# with_usb_small.net
KiCad netlist of a schematic drawn in EAGLE
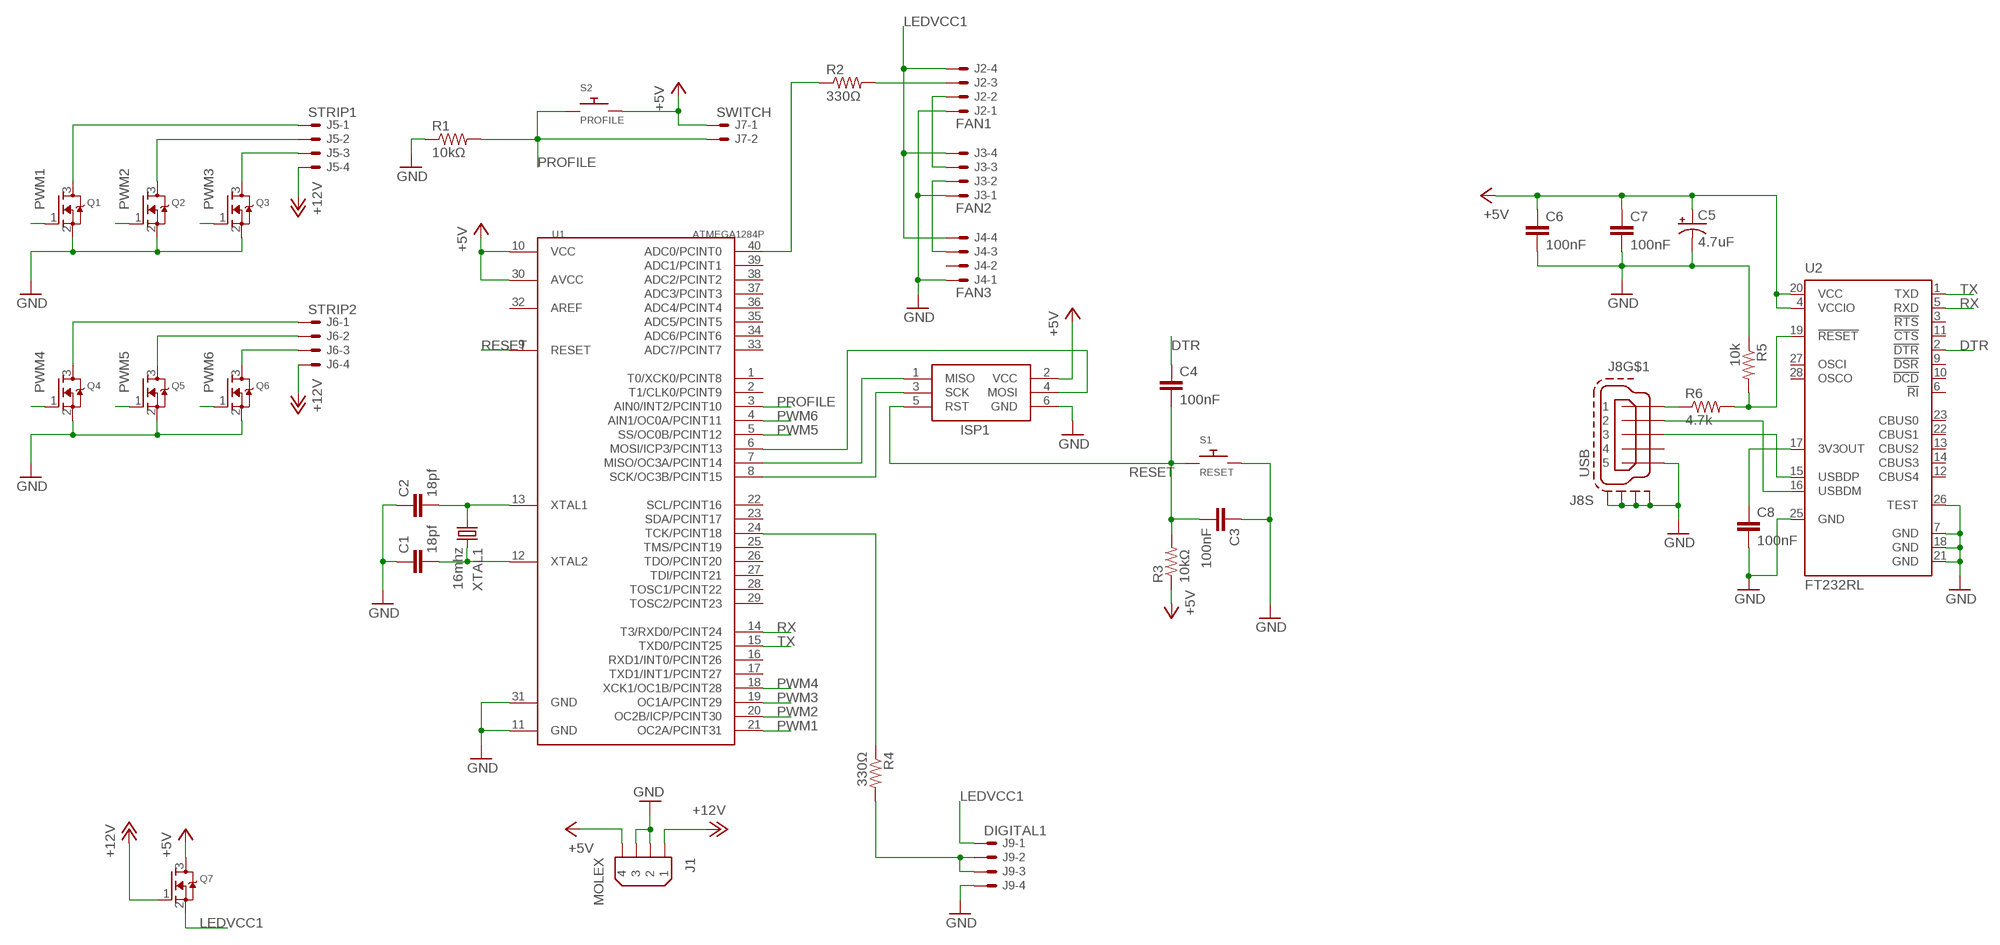
[diagram p0: schematic, sheet 1]

(export (version "E")
  (design (tool "Eeschema 10.0.6"))
  (components
    (comp (ref "C1")
      (value "18pf")
      (footprint "eagle-import:C0805")
      (libsource (lib "eagle-import") (part "C-EUC0805"))
    )
    (comp (ref "C2")
      (value "18pf")
      (footprint "eagle-import:C0805")
      (libsource (lib "eagle-import") (part "C"))
    )
    (comp (ref "C3")
      (value "100nF")
      (footprint "eagle-import:C0805")
      (libsource (lib "eagle-import") (part "C-EUC0805"))
    )
    (comp (ref "C4")
      (value "100nF")
      (footprint "eagle-import:C0805")
      (libsource (lib "eagle-import") (part "C-EUC0805"))
    )
    (comp (ref "C5")
      (value "4.7uF")
      (footprint "eagle-import:153CLV-0505")
      (libsource (lib "eagle-import") (part "CPOL-US153CLV-0505"))
    )
    (comp (ref "C6")
      (value "100nF")
      (footprint "eagle-import:C0805")
      (libsource (lib "eagle-import") (part "resistor_348_C-EUC0805"))
    )
    (comp (ref "C7")
      (value "100nF")
      (footprint "eagle-import:C0805")
      (libsource (lib "eagle-import") (part "resistor_348_C-EUC0805"))
    )
    (comp (ref "C8")
      (value "100nF")
      (footprint "eagle-import:C0805")
      (libsource (lib "eagle-import") (part "resistor_348_C-EUC0805"))
    )
    (comp (ref "ISP1")
      (value "AVRISP-6")
      (footprint "eagle-import:AVRISP")
      (libsource (lib "eagle-import") (part "AVRISP-6"))
    )
    (comp (ref "J1")
      (value "MOLEX")
      (footprint "eagle-import:9090-4R")
      (libsource (lib "eagle-import") (part "9090-4R"))
    )
    (comp (ref "J2")
      (value "FAN1")
      (footprint "eagle-import:22-23-2041")
      (fields (field (name "MF") "MOLEX") (field (name "MPN") "22-23-2041"))
      (libsource (lib "eagle-import") (part "22-23-2041"))
    )
    (comp (ref "J3")
      (value "FAN2")
      (footprint "eagle-import:22-23-2041")
      (fields (field (name "MF") "MOLEX") (field (name "MPN") "22-23-2041"))
      (libsource (lib "eagle-import") (part "22-23-2041"))
    )
    (comp (ref "J4")
      (value "FAN3")
      (footprint "eagle-import:22-23-2041")
      (fields (field (name "MF") "MOLEX") (field (name "MPN") "22-23-2041"))
      (libsource (lib "eagle-import") (part "22-23-2041"))
    )
    (comp (ref "J5")
      (value "STRIP1")
      (footprint "eagle-import:22-23-2041")
      (fields (field (name "MF") "MOLEX") (field (name "MPN") "22-23-2041"))
      (libsource (lib "eagle-import") (part "22-23-2041"))
    )
    (comp (ref "J6")
      (value "STRIP2")
      (footprint "eagle-import:22-23-2041")
      (fields (field (name "MF") "MOLEX") (field (name "MPN") "22-23-2041"))
      (libsource (lib "eagle-import") (part "22-23-2041"))
    )
    (comp (ref "J7")
      (value "SWITCH")
      (footprint "eagle-import:22-23-2021")
      (fields (field (name "MF") "MOLEX") (field (name "MPN") "22-23-2021"))
      (libsource (lib "eagle-import") (part "22-23-2021"))
    )
    (comp (ref "J8")
      (value "USB")
      (footprint "eagle-import:32005-201")
      (libsource (lib "eagle-import") (part "MINI-USB-SCHIELD-32005-201"))
    )
    (comp (ref "J9")
      (value "DIGITAL1")
      (footprint "eagle-import:22-23-2041")
      (fields (field (name "MF") "MOLEX") (field (name "MPN") "22-23-2041"))
      (libsource (lib "eagle-import") (part "22-23-2041"))
    )
    (comp (ref "Q1")
      (value "MOSFET-NREFLOW")
      (footprint "eagle-import:SOT23")
      (libsource (lib "eagle-import") (part "MOSFET-NREFLOW"))
    )
    (comp (ref "Q2")
      (value "MOSFET-NREFLOW")
      (footprint "eagle-import:SOT23")
      (libsource (lib "eagle-import") (part "MOSFET-NREFLOW"))
    )
    (comp (ref "Q3")
      (value "MOSFET-NREFLOW")
      (footprint "eagle-import:SOT23")
      (libsource (lib "eagle-import") (part "MOSFET-NREFLOW"))
    )
    (comp (ref "Q4")
      (value "MOSFET-NREFLOW")
      (footprint "eagle-import:SOT23")
      (libsource (lib "eagle-import") (part "MOSFET-NREFLOW"))
    )
    (comp (ref "Q5")
      (value "MOSFET-NREFLOW")
      (footprint "eagle-import:SOT23")
      (libsource (lib "eagle-import") (part "MOSFET-NREFLOW"))
    )
    (comp (ref "Q6")
      (value "MOSFET-NREFLOW")
      (footprint "eagle-import:SOT23")
      (libsource (lib "eagle-import") (part "MOSFET-NREFLOW"))
    )
    (comp (ref "Q7")
      (value "MOSFET-NREFLOW")
      (footprint "eagle-import:SOT23")
      (libsource (lib "eagle-import") (part "MOSFET-NREFLOW"))
    )
    (comp (ref "R1")
      (value "10kΩ")
      (footprint "eagle-import:M0805")
      (libsource (lib "eagle-import") (part "R-US_M0805"))
    )
    (comp (ref "R2")
      (value "330Ω")
      (footprint "eagle-import:M0805")
      (libsource (lib "eagle-import") (part "R-US_M0805"))
    )
    (comp (ref "R3")
      (value "10kΩ")
      (footprint "eagle-import:M0805")
      (libsource (lib "eagle-import") (part "R-US_M0805"))
    )
    (comp (ref "R4")
      (value "330Ω")
      (footprint "eagle-import:M0805")
      (libsource (lib "eagle-import") (part "R-US_M0805"))
    )
    (comp (ref "R5")
      (value "10k")
      (footprint "eagle-import:R0805")
      (libsource (lib "eagle-import") (part "resistor_348_R-US_R0805"))
    )
    (comp (ref "R6")
      (value "4.7k")
      (footprint "eagle-import:R0805")
      (libsource (lib "eagle-import") (part "resistor_348_R-US_R0805"))
    )
    (comp (ref "S1")
      (value "RESET")
      (footprint "eagle-import:B3F-1000")
      (libsource (lib "eagle-import") (part "BUTTON"))
    )
    (comp (ref "S2")
      (value "PROFILE")
      (footprint "eagle-import:B3F-1000")
      (libsource (lib "eagle-import") (part "BUTTON"))
    )
    (comp (ref "U1")
      (value "ATMEGA1284P")
      (footprint "eagle-import:DIL40")
      (libsource (lib "eagle-import") (part "MEGA1284P"))
    )
    (comp (ref "U2")
      (value "FT232RL")
      (footprint "eagle-import:SSOP28")
      (libsource (lib "eagle-import") (part "FT232RL"))
    )
    (comp (ref "XTAL1")
      (value "16mhz")
      (footprint "eagle-import:HC49U-V")
      (libsource (lib "eagle-import") (part "CRYSTALHC49U-V"))
    )
  )
  (nets
    (net (code "1") (name "+5V") (class "Default")
      (node (ref "C5") (pin "+") (pinfunction "+_+") (pintype "passive"))
      (node (ref "C6") (pin "1") (pinfunction "1_1") (pintype "passive"))
      (node (ref "C7") (pin "1") (pinfunction "1_1") (pintype "passive"))
      (node (ref "ISP1") (pin "2") (pinfunction "VCC_2") (pintype "power_in"))
      (node (ref "J1") (pin "4") (pinfunction "4_4") (pintype "passive"))
      (node (ref "J7") (pin "1") (pinfunction "S_1") (pintype "passive"))
      (node (ref "Q7") (pin "3") (pinfunction "D_3") (pintype "bidirectional"))
      (node (ref "R3") (pin "1") (pinfunction "1_1") (pintype "passive"))
      (node (ref "S2") (pin "3") (pinfunction "P$2_3") (pintype "passive"))
      (node (ref "S2") (pin "4") (pinfunction "P$2_4") (pintype "passive"))
      (node (ref "U1") (pin "10") (pinfunction "VCC_10") (pintype "bidirectional"))
      (node (ref "U1") (pin "30") (pinfunction "AVCC_30") (pintype "bidirectional"))
      (node (ref "U2") (pin "20") (pinfunction "VCC_20") (pintype "power_in"))
      (node (ref "U2") (pin "4") (pinfunction "VCCIO_4") (pintype "power_in"))
    )
    (net (code "2") (name "+12V") (class "Default")
      (node (ref "J1") (pin "1") (pinfunction "1_1") (pintype "passive"))
      (node (ref "J5") (pin "4") (pinfunction "S_4") (pintype "passive"))
      (node (ref "J6") (pin "4") (pinfunction "S_4") (pintype "passive"))
      (node (ref "Q7") (pin "1") (pinfunction "G_1") (pintype "bidirectional"))
    )
    (net (code "3") (name "/DTR") (class "Default")
      (node (ref "C4") (pin "1") (pinfunction "1_1") (pintype "passive"))
      (node (ref "U2") (pin "2") (pinfunction "~{DTR}_2") (pintype "output"))
    )
    (net (code "4") (name "/LEDVCC1") (class "Default")
      (node (ref "J2") (pin "4") (pinfunction "S_4") (pintype "passive"))
      (node (ref "J3") (pin "4") (pinfunction "S_4") (pintype "passive"))
      (node (ref "J4") (pin "4") (pinfunction "S_4") (pintype "passive"))
      (node (ref "J9") (pin "1") (pinfunction "S_1") (pintype "passive"))
      (node (ref "Q7") (pin "2") (pinfunction "S_2") (pintype "bidirectional"))
    )
    (net (code "5") (name "/PROFILE") (class "Default")
      (node (ref "J7") (pin "2") (pinfunction "S_2") (pintype "passive"))
      (node (ref "R1") (pin "2") (pinfunction "2_2") (pintype "passive"))
      (node (ref "S2") (pin "1") (pinfunction "P$1_1") (pintype "passive"))
      (node (ref "S2") (pin "2") (pinfunction "P$1_2") (pintype "passive"))
      (node (ref "U1") (pin "3") (pinfunction "AIN0/INT2/PCINT10_3") (pintype "bidirectional"))
    )
    (net (code "6") (name "/PWM1") (class "Default")
      (node (ref "Q1") (pin "1") (pinfunction "G_1") (pintype "bidirectional"))
      (node (ref "U1") (pin "21") (pinfunction "OC2A/PCINT31_21") (pintype "bidirectional"))
    )
    (net (code "7") (name "/PWM2") (class "Default")
      (node (ref "Q2") (pin "1") (pinfunction "G_1") (pintype "bidirectional"))
      (node (ref "U1") (pin "20") (pinfunction "OC2B/ICP/PCINT30_20") (pintype "bidirectional"))
    )
    (net (code "8") (name "/PWM3") (class "Default")
      (node (ref "Q3") (pin "1") (pinfunction "G_1") (pintype "bidirectional"))
      (node (ref "U1") (pin "19") (pinfunction "OC1A/PCINT29_19") (pintype "bidirectional"))
    )
    (net (code "9") (name "/PWM4") (class "Default")
      (node (ref "Q4") (pin "1") (pinfunction "G_1") (pintype "bidirectional"))
      (node (ref "U1") (pin "18") (pinfunction "XCK1/OC1B/PCINT28_18") (pintype "bidirectional"))
    )
    (net (code "10") (name "/PWM5") (class "Default")
      (node (ref "Q5") (pin "1") (pinfunction "G_1") (pintype "bidirectional"))
      (node (ref "U1") (pin "5") (pinfunction "SS/OC0B/PCINT12_5") (pintype "bidirectional"))
    )
    (net (code "11") (name "/PWM6") (class "Default")
      (node (ref "Q6") (pin "1") (pinfunction "G_1") (pintype "bidirectional"))
      (node (ref "U1") (pin "4") (pinfunction "AIN1/OC0A/PCINT11_4") (pintype "bidirectional"))
    )
    (net (code "12") (name "/RESET") (class "Default")
      (node (ref "C3") (pin "2") (pinfunction "2_2") (pintype "passive"))
      (node (ref "C4") (pin "2") (pinfunction "2_2") (pintype "passive"))
      (node (ref "ISP1") (pin "5") (pinfunction "RST_5") (pintype "output"))
      (node (ref "R3") (pin "2") (pinfunction "2_2") (pintype "passive"))
      (node (ref "S1") (pin "1") (pinfunction "P$1_1") (pintype "passive"))
      (node (ref "S1") (pin "2") (pinfunction "P$1_2") (pintype "passive"))
      (node (ref "U1") (pin "9") (pinfunction "RESET_9") (pintype "bidirectional"))
    )
    (net (code "13") (name "/RX") (class "Default")
      (node (ref "U1") (pin "14") (pinfunction "T3/RXD0/PCINT24_14") (pintype "bidirectional"))
      (node (ref "U2") (pin "5") (pinfunction "RXD_5") (pintype "input"))
    )
    (net (code "14") (name "/TX") (class "Default")
      (node (ref "U1") (pin "15") (pinfunction "TXD0/PCINT25_15") (pintype "bidirectional"))
      (node (ref "U2") (pin "1") (pinfunction "TXD_1") (pintype "output"))
    )
    (net (code "15") (name "GND") (class "Default")
      (node (ref "C1") (pin "1") (pinfunction "1_1") (pintype "passive"))
      (node (ref "C2") (pin "1") (pinfunction "1_1") (pintype "passive"))
      (node (ref "C3") (pin "1") (pinfunction "1_1") (pintype "passive"))
      (node (ref "C5") (pin "-") (pinfunction "-_-") (pintype "passive"))
      (node (ref "C6") (pin "2") (pinfunction "2_2") (pintype "passive"))
      (node (ref "C7") (pin "2") (pinfunction "2_2") (pintype "passive"))
      (node (ref "C8") (pin "2") (pinfunction "2_2") (pintype "passive"))
      (node (ref "ISP1") (pin "6") (pinfunction "GND_6") (pintype "power_in"))
      (node (ref "J1") (pin "2") (pinfunction "2_2") (pintype "passive"))
      (node (ref "J1") (pin "3") (pinfunction "3_3") (pintype "passive"))
      (node (ref "J2") (pin "1") (pinfunction "S_1") (pintype "passive"))
      (node (ref "J3") (pin "1") (pinfunction "S_1") (pintype "passive"))
      (node (ref "J4") (pin "1") (pinfunction "S_1") (pintype "passive"))
      (node (ref "J8") (pin "5") (pinfunction "5_5") (pintype "passive"))
      (node (ref "J8") (pin "M1") (pinfunction "S1_M1") (pintype "passive"))
      (node (ref "J8") (pin "M2") (pinfunction "S2_M2") (pintype "passive"))
      (node (ref "J8") (pin "M3") (pinfunction "S3_M3") (pintype "passive"))
      (node (ref "J8") (pin "M4") (pinfunction "S4_M4") (pintype "passive"))
      (node (ref "J9") (pin "4") (pinfunction "S_4") (pintype "passive"))
      (node (ref "Q1") (pin "2") (pinfunction "S_2") (pintype "bidirectional"))
      (node (ref "Q2") (pin "2") (pinfunction "S_2") (pintype "bidirectional"))
      (node (ref "Q3") (pin "2") (pinfunction "S_2") (pintype "bidirectional"))
      (node (ref "Q4") (pin "2") (pinfunction "S_2") (pintype "bidirectional"))
      (node (ref "Q5") (pin "2") (pinfunction "S_2") (pintype "bidirectional"))
      (node (ref "Q6") (pin "2") (pinfunction "S_2") (pintype "bidirectional"))
      (node (ref "R1") (pin "1") (pinfunction "1_1") (pintype "passive"))
      (node (ref "R5") (pin "1") (pinfunction "1_1") (pintype "passive"))
      (node (ref "S1") (pin "3") (pinfunction "P$2_3") (pintype "passive"))
      (node (ref "S1") (pin "4") (pinfunction "P$2_4") (pintype "passive"))
      (node (ref "U1") (pin "11") (pinfunction "GND_11") (pintype "bidirectional"))
      (node (ref "U1") (pin "31") (pinfunction "GND_31") (pintype "bidirectional"))
      (node (ref "U2") (pin "18") (pinfunction "GND_18") (pintype "power_in"))
      (node (ref "U2") (pin "21") (pinfunction "GND_21") (pintype "power_in"))
      (node (ref "U2") (pin "25") (pinfunction "GND_25") (pintype "power_in"))
      (node (ref "U2") (pin "26") (pinfunction "TEST_26") (pintype "input"))
      (node (ref "U2") (pin "7") (pinfunction "GND_7") (pintype "power_in"))
    )
    (net (code "16") (name "Net-(ISP1-MISO)") (class "Default")
      (node (ref "ISP1") (pin "1") (pinfunction "MISO_1") (pintype "input"))
      (node (ref "U1") (pin "7") (pinfunction "MISO/OC3A/PCINT14_7") (pintype "bidirectional"))
    )
    (net (code "17") (name "Net-(ISP1-MOSI)") (class "Default")
      (node (ref "ISP1") (pin "4") (pinfunction "MOSI_4") (pintype "output"))
      (node (ref "U1") (pin "6") (pinfunction "MOSI/ICP3/PCINT13_6") (pintype "bidirectional"))
    )
    (net (code "18") (name "Net-(ISP1-SCK)") (class "Default")
      (node (ref "ISP1") (pin "3") (pinfunction "SCK_3") (pintype "output"))
      (node (ref "U1") (pin "8") (pinfunction "SCK/OC3B/PCINT15_8") (pintype "bidirectional"))
    )
    (net (code "19") (name "Net-(J2B-S)") (class "Default")
      (node (ref "J2") (pin "2") (pinfunction "S_2") (pintype "passive"))
      (node (ref "J3") (pin "3") (pinfunction "S_3") (pintype "passive"))
    )
    (net (code "20") (name "Net-(J2C-S)") (class "Default")
      (node (ref "J2") (pin "3") (pinfunction "S_3") (pintype "passive"))
      (node (ref "R2") (pin "2") (pinfunction "2_2") (pintype "passive"))
    )
    (net (code "21") (name "Net-(J3B-S)") (class "Default")
      (node (ref "J3") (pin "2") (pinfunction "S_2") (pintype "passive"))
      (node (ref "J4") (pin "3") (pinfunction "S_3") (pintype "passive"))
    )
    (net (code "22") (name "Net-(J5A-S)") (class "Default")
      (node (ref "J5") (pin "1") (pinfunction "S_1") (pintype "passive"))
      (node (ref "Q1") (pin "3") (pinfunction "D_3") (pintype "bidirectional"))
    )
    (net (code "23") (name "Net-(J5B-S)") (class "Default")
      (node (ref "J5") (pin "2") (pinfunction "S_2") (pintype "passive"))
      (node (ref "Q2") (pin "3") (pinfunction "D_3") (pintype "bidirectional"))
    )
    (net (code "24") (name "Net-(J5C-S)") (class "Default")
      (node (ref "J5") (pin "3") (pinfunction "S_3") (pintype "passive"))
      (node (ref "Q3") (pin "3") (pinfunction "D_3") (pintype "bidirectional"))
    )
    (net (code "25") (name "Net-(J6A-S)") (class "Default")
      (node (ref "J6") (pin "1") (pinfunction "S_1") (pintype "passive"))
      (node (ref "Q4") (pin "3") (pinfunction "D_3") (pintype "bidirectional"))
    )
    (net (code "26") (name "Net-(J6B-S)") (class "Default")
      (node (ref "J6") (pin "2") (pinfunction "S_2") (pintype "passive"))
      (node (ref "Q5") (pin "3") (pinfunction "D_3") (pintype "bidirectional"))
    )
    (net (code "27") (name "Net-(J6C-S)") (class "Default")
      (node (ref "J6") (pin "3") (pinfunction "S_3") (pintype "passive"))
      (node (ref "Q6") (pin "3") (pinfunction "D_3") (pintype "bidirectional"))
    )
    (net (code "28") (name "Net-(J8-Pad1)") (class "Default")
      (node (ref "J8") (pin "1") (pinfunction "1_1") (pintype "passive"))
      (node (ref "R6") (pin "1") (pinfunction "1_1") (pintype "passive"))
    )
    (net (code "29") (name "Net-(J9B-S)") (class "Default")
      (node (ref "J9") (pin "2") (pinfunction "S_2") (pintype "passive"))
      (node (ref "J9") (pin "3") (pinfunction "S_3") (pintype "passive"))
      (node (ref "R4") (pin "2") (pinfunction "2_2") (pintype "passive"))
    )
    (net (code "30") (name "Net-(U1-ADC0{slash}PCINT0)") (class "Default")
      (node (ref "R2") (pin "1") (pinfunction "1_1") (pintype "passive"))
      (node (ref "U1") (pin "40") (pinfunction "ADC0/PCINT0_40") (pintype "bidirectional"))
    )
    (net (code "31") (name "Net-(U1-TCK{slash}PCINT18)") (class "Default")
      (node (ref "R4") (pin "1") (pinfunction "1_1") (pintype "passive"))
      (node (ref "U1") (pin "24") (pinfunction "TCK/PCINT18_24") (pintype "bidirectional"))
    )
    (net (code "32") (name "Net-(U1-XTAL1)") (class "Default")
      (node (ref "C2") (pin "2") (pinfunction "2_2") (pintype "passive"))
      (node (ref "U1") (pin "13") (pinfunction "XTAL1_13") (pintype "bidirectional"))
      (node (ref "XTAL1") (pin "1") (pinfunction "1_1") (pintype "passive"))
    )
    (net (code "33") (name "Net-(U1-XTAL2)") (class "Default")
      (node (ref "C1") (pin "2") (pinfunction "2_2") (pintype "passive"))
      (node (ref "U1") (pin "12") (pinfunction "XTAL2_12") (pintype "bidirectional"))
      (node (ref "XTAL1") (pin "2") (pinfunction "2_2") (pintype "passive"))
    )
    (net (code "34") (name "Net-(U2-3V3OUT)") (class "Default")
      (node (ref "C8") (pin "1") (pinfunction "1_1") (pintype "passive"))
      (node (ref "U2") (pin "17") (pinfunction "3V3OUT_17") (pintype "output"))
    )
    (net (code "35") (name "Net-(U2-USBDM)") (class "Default")
      (node (ref "J8") (pin "2") (pinfunction "2_2") (pintype "passive"))
      (node (ref "U2") (pin "16") (pinfunction "USBDM_16") (pintype "bidirectional"))
    )
    (net (code "36") (name "Net-(U2-USBDP)") (class "Default")
      (node (ref "J8") (pin "3") (pinfunction "3_3") (pintype "passive"))
      (node (ref "U2") (pin "15") (pinfunction "USBDP_15") (pintype "bidirectional"))
    )
    (net (code "37") (name "Net-(U2-~{RESET})") (class "Default")
      (node (ref "R5") (pin "2") (pinfunction "2_2") (pintype "passive"))
      (node (ref "R6") (pin "2") (pinfunction "2_2") (pintype "passive"))
      (node (ref "U2") (pin "19") (pinfunction "~{RESET}_19") (pintype "input"))
    )
    (net (code "38") (name "unconnected-(J4B-S-Pad2)") (class "Default")
      (node (ref "J4") (pin "2") (pinfunction "S_2") (pintype "passive"))
    )
    (net (code "39") (name "unconnected-(J8-Pad4)") (class "Default")
      (node (ref "J8") (pin "4") (pinfunction "4_4") (pintype "passive"))
    )
    (net (code "40") (name "unconnected-(U1-ADC1{slash}PCINT1-Pad39)") (class "Default")
      (node (ref "U1") (pin "39") (pinfunction "ADC1/PCINT1_39") (pintype "bidirectional"))
    )
    (net (code "41") (name "unconnected-(U1-ADC2{slash}PCINT2-Pad38)") (class "Default")
      (node (ref "U1") (pin "38") (pinfunction "ADC2/PCINT2_38") (pintype "bidirectional"))
    )
    (net (code "42") (name "unconnected-(U1-ADC3{slash}PCINT3-Pad37)") (class "Default")
      (node (ref "U1") (pin "37") (pinfunction "ADC3/PCINT3_37") (pintype "bidirectional"))
    )
    (net (code "43") (name "unconnected-(U1-ADC4{slash}PCINT4-Pad36)") (class "Default")
      (node (ref "U1") (pin "36") (pinfunction "ADC4/PCINT4_36") (pintype "bidirectional"))
    )
    (net (code "44") (name "unconnected-(U1-ADC5{slash}PCINT5-Pad35)") (class "Default")
      (node (ref "U1") (pin "35") (pinfunction "ADC5/PCINT5_35") (pintype "bidirectional"))
    )
    (net (code "45") (name "unconnected-(U1-ADC6{slash}PCINT6-Pad34)") (class "Default")
      (node (ref "U1") (pin "34") (pinfunction "ADC6/PCINT6_34") (pintype "bidirectional"))
    )
    (net (code "46") (name "unconnected-(U1-ADC7{slash}PCINT7-Pad33)") (class "Default")
      (node (ref "U1") (pin "33") (pinfunction "ADC7/PCINT7_33") (pintype "bidirectional"))
    )
    (net (code "47") (name "unconnected-(U1-AREF-Pad32)") (class "Default")
      (node (ref "U1") (pin "32") (pinfunction "AREF_32") (pintype "bidirectional"))
    )
    (net (code "48") (name "unconnected-(U1-RXD1{slash}INT0{slash}PCINT26-Pad16)") (class "Default")
      (node (ref "U1") (pin "16") (pinfunction "RXD1/INT0/PCINT26_16") (pintype "bidirectional"))
    )
    (net (code "49") (name "unconnected-(U1-SCL{slash}PCINT16-Pad22)") (class "Default")
      (node (ref "U1") (pin "22") (pinfunction "SCL/PCINT16_22") (pintype "bidirectional"))
    )
    (net (code "50") (name "unconnected-(U1-SDA{slash}PCINT17-Pad23)") (class "Default")
      (node (ref "U1") (pin "23") (pinfunction "SDA/PCINT17_23") (pintype "bidirectional"))
    )
    (net (code "51") (name "unconnected-(U1-T0{slash}XCK0{slash}PCINT8-Pad1)") (class "Default")
      (node (ref "U1") (pin "1") (pinfunction "T0/XCK0/PCINT8_1") (pintype "bidirectional"))
    )
    (net (code "52") (name "unconnected-(U1-T1{slash}CLK0{slash}PCINT9-Pad2)") (class "Default")
      (node (ref "U1") (pin "2") (pinfunction "T1/CLK0/PCINT9_2") (pintype "bidirectional"))
    )
    (net (code "53") (name "unconnected-(U1-TDI{slash}PCINT21-Pad27)") (class "Default")
      (node (ref "U1") (pin "27") (pinfunction "TDI/PCINT21_27") (pintype "bidirectional"))
    )
    (net (code "54") (name "unconnected-(U1-TDO{slash}PCINT20-Pad26)") (class "Default")
      (node (ref "U1") (pin "26") (pinfunction "TDO/PCINT20_26") (pintype "bidirectional"))
    )
    (net (code "55") (name "unconnected-(U1-TMS{slash}PCINT19-Pad25)") (class "Default")
      (node (ref "U1") (pin "25") (pinfunction "TMS/PCINT19_25") (pintype "bidirectional"))
    )
    (net (code "56") (name "unconnected-(U1-TOSC1{slash}PCINT22-Pad28)") (class "Default")
      (node (ref "U1") (pin "28") (pinfunction "TOSC1/PCINT22_28") (pintype "bidirectional"))
    )
    (net (code "57") (name "unconnected-(U1-TOSC2{slash}PCINT23-Pad29)") (class "Default")
      (node (ref "U1") (pin "29") (pinfunction "TOSC2/PCINT23_29") (pintype "bidirectional"))
    )
    (net (code "58") (name "unconnected-(U1-TXD1{slash}INT1{slash}PCINT27-Pad17)") (class "Default")
      (node (ref "U1") (pin "17") (pinfunction "TXD1/INT1/PCINT27_17") (pintype "bidirectional"))
    )
    (net (code "59") (name "unconnected-(U2-CBUS0-Pad23)") (class "Default")
      (node (ref "U2") (pin "23") (pinfunction "CBUS0_23") (pintype "bidirectional"))
    )
    (net (code "60") (name "unconnected-(U2-CBUS1-Pad22)") (class "Default")
      (node (ref "U2") (pin "22") (pinfunction "CBUS1_22") (pintype "bidirectional"))
    )
    (net (code "61") (name "unconnected-(U2-CBUS2-Pad13)") (class "Default")
      (node (ref "U2") (pin "13") (pinfunction "CBUS2_13") (pintype "bidirectional"))
    )
    (net (code "62") (name "unconnected-(U2-CBUS3-Pad14)") (class "Default")
      (node (ref "U2") (pin "14") (pinfunction "CBUS3_14") (pintype "bidirectional"))
    )
    (net (code "63") (name "unconnected-(U2-CBUS4-Pad12)") (class "Default")
      (node (ref "U2") (pin "12") (pinfunction "CBUS4_12") (pintype "bidirectional"))
    )
    (net (code "64") (name "unconnected-(U2-OSCI-Pad27)") (class "Default")
      (node (ref "U2") (pin "27") (pinfunction "OSCI_27") (pintype "input"))
    )
    (net (code "65") (name "unconnected-(U2-OSCO-Pad28)") (class "Default")
      (node (ref "U2") (pin "28") (pinfunction "OSCO_28") (pintype "output"))
    )
    (net (code "66") (name "unconnected-(U2-~{CTS}-Pad11)") (class "Default")
      (node (ref "U2") (pin "11") (pinfunction "~{CTS}_11") (pintype "input"))
    )
    (net (code "67") (name "unconnected-(U2-~{DCD}-Pad10)") (class "Default")
      (node (ref "U2") (pin "10") (pinfunction "~{DCD}_10") (pintype "input"))
    )
    (net (code "68") (name "unconnected-(U2-~{DSR}-Pad9)") (class "Default")
      (node (ref "U2") (pin "9") (pinfunction "~{DSR}_9") (pintype "input"))
    )
    (net (code "69") (name "unconnected-(U2-~{RI}-Pad6)") (class "Default")
      (node (ref "U2") (pin "6") (pinfunction "~{RI}_6") (pintype "input"))
    )
    (net (code "70") (name "unconnected-(U2-~{RTS}-Pad3)") (class "Default")
      (node (ref "U2") (pin "3") (pinfunction "~{RTS}_3") (pintype "output"))
    )
  )
)
